# 2020_IST_Respirator_v1_1.net
KiCad netlist of a schematic drawn in EAGLE
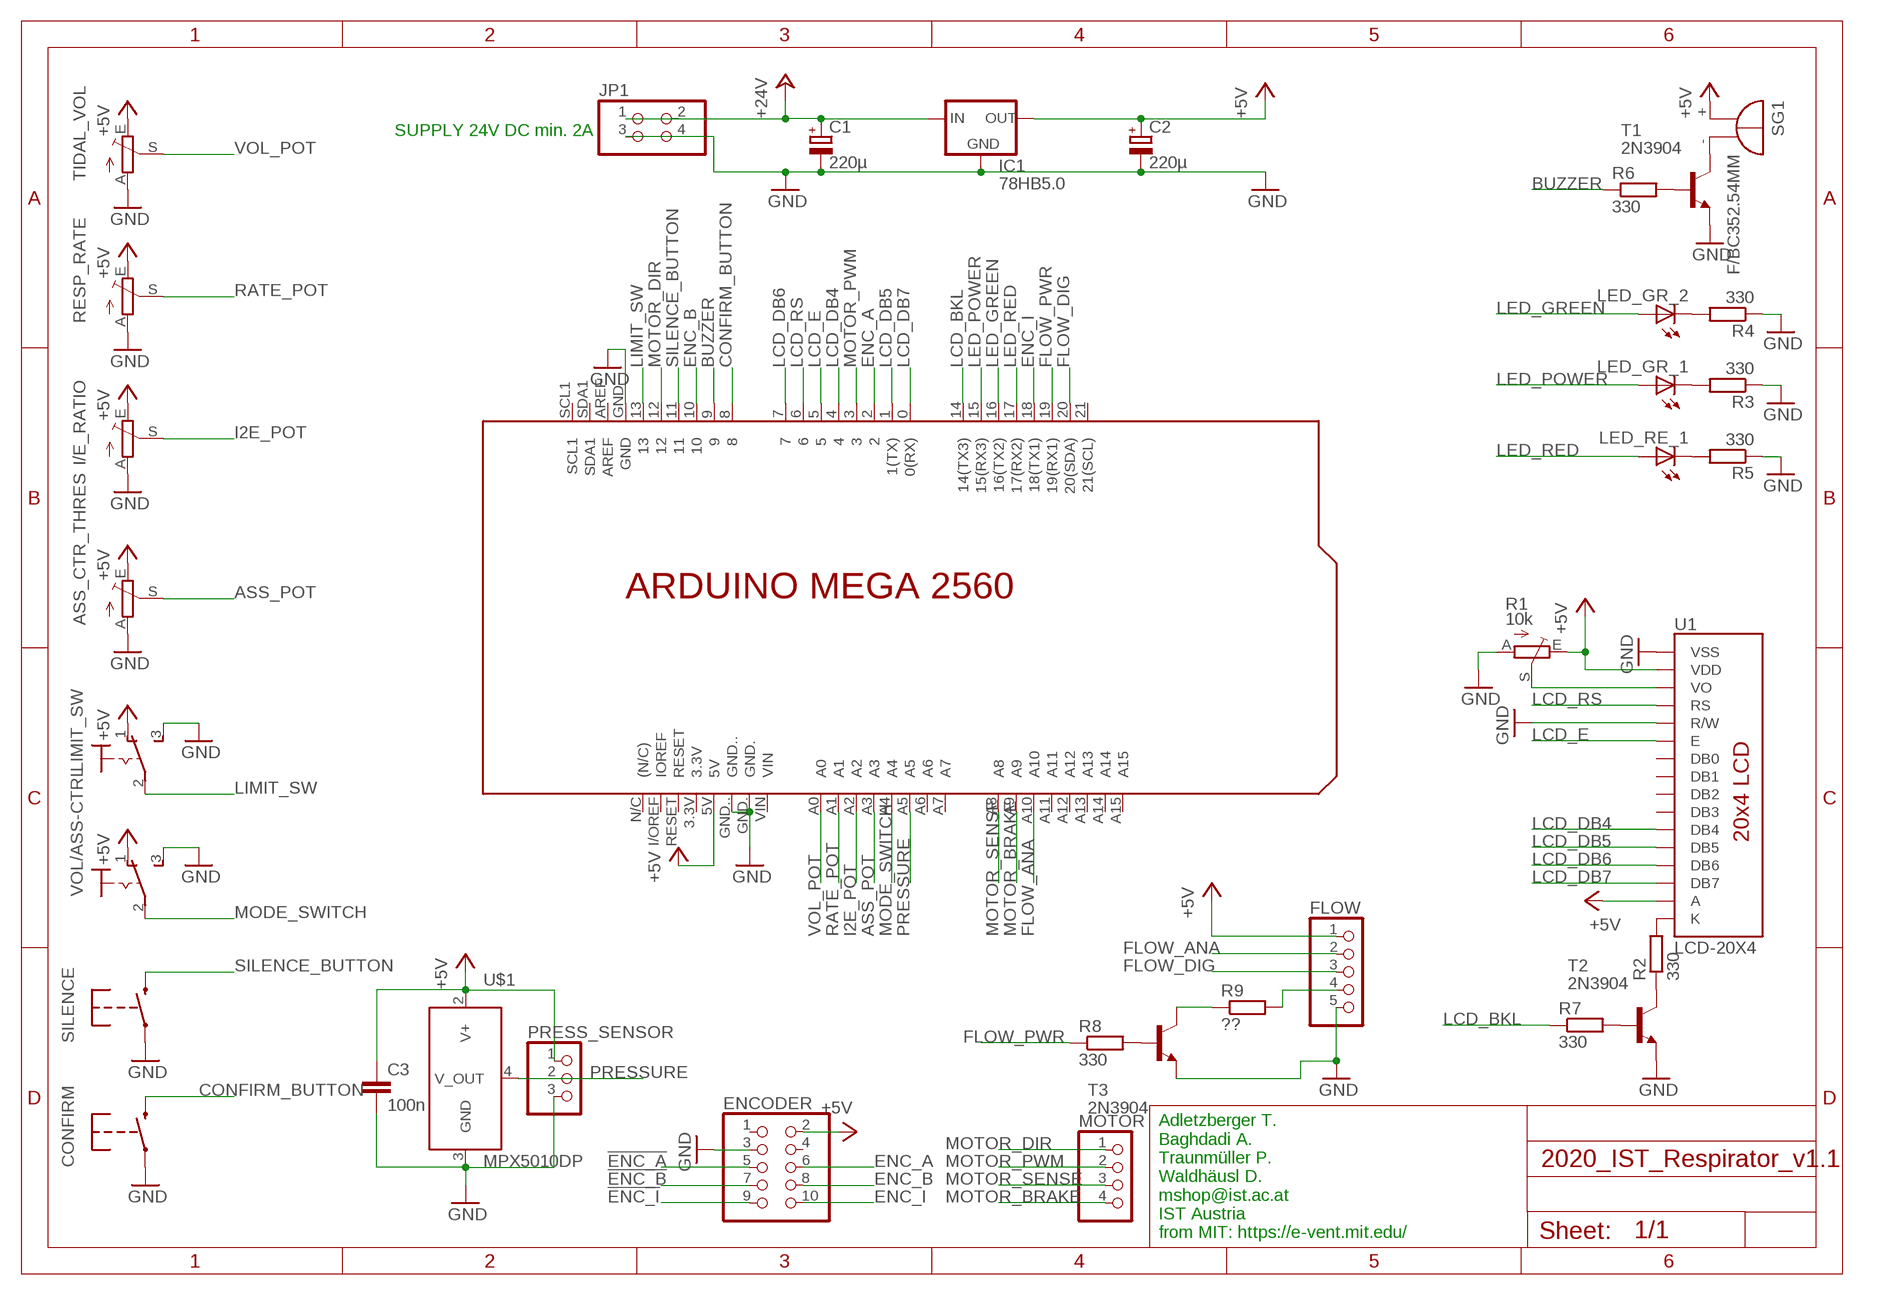
[diagram p0: schematic, sheet 1]

(export (version "E")
  (design (tool "Eeschema 10.0.6"))
  (components
    (comp (ref "ASS_CTR_THRES")
      (value "TRIM_EU-S64W")
      (footprint "eagle-import:S64W")
      (libsource (lib "eagle-import") (part "TRIM_EU-S64W"))
    )
    (comp (ref "C1")
      (value "220µ")
      (footprint "eagle-import:E5-10,5")
      (libsource (lib "eagle-import") (part "CPOL-EUE5-10.5"))
    )
    (comp (ref "C2")
      (value "220µ")
      (footprint "eagle-import:E5-10,5")
      (libsource (lib "eagle-import") (part "CPOL-EUE5-10.5"))
    )
    (comp (ref "C3")
      (value "100n")
      (footprint "eagle-import:C0805")
      (libsource (lib "eagle-import") (part "C-EUC0805"))
    )
    (comp (ref "CONFIRM")
      (value "SWITCH-MOMENTARY-22.54")
      (footprint "eagle-import:TACTILE-2.54MM")
      (libsource (lib "eagle-import") (part "SWITCH-MOMENTARY-22.54"))
    )
    (comp (ref "ENCODER")
      (value "PINHD-2X5")
      (footprint "eagle-import:2X05")
      (libsource (lib "eagle-import") (part "PINHD-2X5"))
    )
    (comp (ref "FLOW")
      (value "PINHD-1X5")
      (footprint "eagle-import:1X05")
      (libsource (lib "eagle-import") (part "PINHD-1X5"))
    )
    (comp (ref "I/E_RATIO")
      (value "TRIM_EU-S64W")
      (footprint "eagle-import:S64W")
      (libsource (lib "eagle-import") (part "TRIM_EU-S64W"))
    )
    (comp (ref "IC1")
      (value "78HB5.0")
      (footprint "eagle-import:78XXS")
      (libsource (lib "eagle-import") (part "78XXS"))
    )
    (comp (ref "JP1")
      (value "PINHD-2X2")
      (footprint "eagle-import:2X02")
      (libsource (lib "eagle-import") (part "PINHD-2X2"))
    )
    (comp (ref "LED_GR_1")
      (value "LED5MM")
      (footprint "eagle-import:LED5MM")
      (libsource (lib "eagle-import") (part "LED5MM"))
    )
    (comp (ref "LED_GR_2")
      (value "LED5MM")
      (footprint "eagle-import:LED5MM")
      (libsource (lib "eagle-import") (part "LED5MM"))
    )
    (comp (ref "LED_RE_1")
      (value "LED5MM")
      (footprint "eagle-import:LED5MM")
      (libsource (lib "eagle-import") (part "LED5MM"))
    )
    (comp (ref "LIMIT_SW")
      (value "320-9162.54MM")
      (footprint "eagle-import:320-916_2.54MM")
      (libsource (lib "eagle-import") (part "320-9162.54MM"))
    )
    (comp (ref "MOTOR")
      (value "PINHD-1X4")
      (footprint "eagle-import:1X04")
      (libsource (lib "eagle-import") (part "PINHD-1X4"))
    )
    (comp (ref "PCB1")
      (value "ARDUINO_MEGA2560_NOTALLPINS")
      (footprint "eagle-import:ARDUINO_MEGA2560_NOTALLPINS")
      (libsource (lib "eagle-import") (part "ARDUINO_MEGA2560_NOTALLPINS"))
    )
    (comp (ref "PRESS_SENSOR")
      (value "PINHD-1X3")
      (footprint "eagle-import:1X03")
      (libsource (lib "eagle-import") (part "PINHD-1X3"))
    )
    (comp (ref "R1")
      (value "10k")
      (footprint "eagle-import:S64W")
      (libsource (lib "eagle-import") (part "TRIM_EU-S64W"))
    )
    (comp (ref "R2")
      (value "330")
      (footprint "eagle-import:0207_10")
      (libsource (lib "eagle-import") (part "R-EU_0207/10"))
    )
    (comp (ref "R3")
      (value "330")
      (footprint "eagle-import:0207_10")
      (libsource (lib "eagle-import") (part "R-EU_0207/10"))
    )
    (comp (ref "R4")
      (value "330")
      (footprint "eagle-import:0207_10")
      (libsource (lib "eagle-import") (part "R-EU_0207/10"))
    )
    (comp (ref "R5")
      (value "330")
      (footprint "eagle-import:0207_10")
      (libsource (lib "eagle-import") (part "R-EU_0207/10"))
    )
    (comp (ref "R6")
      (value "330")
      (footprint "eagle-import:0207_10")
      (libsource (lib "eagle-import") (part "R-EU_0207/10"))
    )
    (comp (ref "R7")
      (value "330")
      (footprint "eagle-import:0207_10")
      (libsource (lib "eagle-import") (part "R-EU_0207/10"))
    )
    (comp (ref "R8")
      (value "330")
      (footprint "eagle-import:0207_10")
      (libsource (lib "eagle-import") (part "R-EU_0207/10"))
    )
    (comp (ref "R9")
      (value "??")
      (footprint "eagle-import:0207_10")
      (libsource (lib "eagle-import") (part "R-EU_0207/10"))
    )
    (comp (ref "RESP_RATE")
      (value "TRIM_EU-S64W")
      (footprint "eagle-import:S64W")
      (libsource (lib "eagle-import") (part "TRIM_EU-S64W"))
    )
    (comp (ref "SG1")
      (value "F/BC352.54MM")
      (footprint "eagle-import:F_BC35_2.54MM")
      (libsource (lib "eagle-import") (part "F/BC352.54MM"))
    )
    (comp (ref "SILENCE")
      (value "SWITCH-MOMENTARY-22.54")
      (footprint "eagle-import:TACTILE-2.54MM")
      (libsource (lib "eagle-import") (part "SWITCH-MOMENTARY-22.54"))
    )
    (comp (ref "T1")
      (value "2N3904")
      (footprint "eagle-import:TO92")
      (libsource (lib "eagle-import") (part "2N3904"))
    )
    (comp (ref "T2")
      (value "2N3904")
      (footprint "eagle-import:TO92")
      (libsource (lib "eagle-import") (part "2N3904"))
    )
    (comp (ref "T3")
      (value "2N3904")
      (footprint "eagle-import:TO92")
      (libsource (lib "eagle-import") (part "2N3904"))
    )
    (comp (ref "TIDAL_VOL")
      (value "TRIM_EU-S64W")
      (footprint "eagle-import:S64W")
      (libsource (lib "eagle-import") (part "TRIM_EU-S64W"))
    )
    (comp (ref "U$1")
      (value "MPX5010DP")
      (footprint "eagle-import:MPX5010DP_SOP482")
      (libsource (lib "eagle-import") (part "MPX5010DP"))
    )
    (comp (ref "U1")
      (value "LCD-20X4")
      (footprint "eagle-import:LCD-20X4")
      (libsource (lib "eagle-import") (part "LCD-20X4"))
    )
    (comp (ref "VOL/ASS-CTRL")
      (value "320-9162.54MM")
      (footprint "eagle-import:320-916_2.54MM")
      (libsource (lib "eagle-import") (part "320-9162.54MM"))
    )
  )
  (nets
    (net (code "1") (name "+5V") (class "Default")
      (node (ref "ASS_CTR_THRES") (pin "E") (pinfunction "E_E") (pintype "passive"))
      (node (ref "C2") (pin "+") (pinfunction "+_+") (pintype "passive"))
      (node (ref "C3") (pin "1") (pinfunction "1_1") (pintype "passive"))
      (node (ref "ENCODER") (pin "2") (pinfunction "2_2") (pintype "passive"))
      (node (ref "FLOW") (pin "1") (pinfunction "1_1") (pintype "passive"))
      (node (ref "I/E_RATIO") (pin "E") (pinfunction "E_E") (pintype "passive"))
      (node (ref "IC1") (pin "OUT") (pinfunction "OUT_OUT") (pintype "passive"))
      (node (ref "LIMIT_SW") (pin "1") (pinfunction "O_1") (pintype "passive"))
      (node (ref "PCB1") (pin "5V") (pinfunction "5V_5V") (pintype "bidirectional"))
      (node (ref "PRESS_SENSOR") (pin "1") (pinfunction "1_1") (pintype "passive"))
      (node (ref "R1") (pin "E") (pinfunction "E_E") (pintype "passive"))
      (node (ref "RESP_RATE") (pin "E") (pinfunction "E_E") (pintype "passive"))
      (node (ref "SG1") (pin "+") (pinfunction "+_+") (pintype "passive"))
      (node (ref "TIDAL_VOL") (pin "E") (pinfunction "E_E") (pintype "passive"))
      (node (ref "U$1") (pin "2") (pinfunction "V+_2") (pintype "power_in"))
      (node (ref "U1") (pin "15") (pinfunction "A_15") (pintype "power_in"))
      (node (ref "U1") (pin "2") (pinfunction "VDD_2") (pintype "power_in"))
      (node (ref "VOL/ASS-CTRL") (pin "1") (pinfunction "O_1") (pintype "passive"))
    )
    (net (code "2") (name "+24V") (class "Default")
      (node (ref "C1") (pin "+") (pinfunction "+_+") (pintype "passive"))
      (node (ref "IC1") (pin "IN") (pinfunction "IN_IN") (pintype "input"))
      (node (ref "JP1") (pin "1") (pinfunction "1_1") (pintype "passive"))
      (node (ref "JP1") (pin "2") (pinfunction "2_2") (pintype "passive"))
    )
    (net (code "3") (name "/ASS_POT") (class "Default")
      (node (ref "ASS_CTR_THRES") (pin "S") (pinfunction "S_S") (pintype "passive"))
      (node (ref "PCB1") (pin "A3") (pinfunction "A3_A3") (pintype "bidirectional"))
    )
    (net (code "4") (name "/BUZZER") (class "Default")
      (node (ref "PCB1") (pin "9") (pinfunction "9_9") (pintype "bidirectional"))
      (node (ref "R6") (pin "1") (pinfunction "1_1") (pintype "passive"))
    )
    (net (code "5") (name "/CONFIRM_BUTTON") (class "Default")
      (node (ref "CONFIRM") (pin "3") (pinfunction "2_3") (pintype "passive"))
      (node (ref "PCB1") (pin "8") (pinfunction "8_8") (pintype "bidirectional"))
    )
    (net (code "6") (name "/ENC_A") (class "Default")
      (node (ref "ENCODER") (pin "6") (pinfunction "6_6") (pintype "passive"))
      (node (ref "PCB1") (pin "2") (pinfunction "2_2") (pintype "bidirectional"))
    )
    (net (code "7") (name "/ENC_B") (class "Default")
      (node (ref "ENCODER") (pin "8") (pinfunction "8_8") (pintype "passive"))
      (node (ref "PCB1") (pin "10") (pinfunction "10_10") (pintype "bidirectional"))
    )
    (net (code "8") (name "/ENC_I") (class "Default")
      (node (ref "ENCODER") (pin "10") (pinfunction "10_10") (pintype "passive"))
      (node (ref "PCB1") (pin "18") (pinfunction "18(TX1)_18") (pintype "bidirectional"))
    )
    (net (code "9") (name "/FLOW_ANA") (class "Default")
      (node (ref "FLOW") (pin "2") (pinfunction "2_2") (pintype "passive"))
      (node (ref "PCB1") (pin "A10") (pinfunction "A10_A10") (pintype "bidirectional"))
    )
    (net (code "10") (name "/FLOW_DIG") (class "Default")
      (node (ref "FLOW") (pin "3") (pinfunction "3_3") (pintype "passive"))
      (node (ref "PCB1") (pin "20") (pinfunction "20(SDA)_20") (pintype "bidirectional"))
    )
    (net (code "11") (name "/FLOW_PWR") (class "Default")
      (node (ref "PCB1") (pin "19") (pinfunction "19(RX1)_19") (pintype "bidirectional"))
      (node (ref "R8") (pin "1") (pinfunction "1_1") (pintype "passive"))
    )
    (net (code "12") (name "/I2E_POT") (class "Default")
      (node (ref "I/E_RATIO") (pin "S") (pinfunction "S_S") (pintype "passive"))
      (node (ref "PCB1") (pin "A2") (pinfunction "A2_A2") (pintype "bidirectional"))
    )
    (net (code "13") (name "/LCD_BKL") (class "Default")
      (node (ref "PCB1") (pin "14") (pinfunction "14(TX3)_14") (pintype "bidirectional"))
      (node (ref "R7") (pin "1") (pinfunction "1_1") (pintype "passive"))
    )
    (net (code "14") (name "/LCD_DB4") (class "Default")
      (node (ref "PCB1") (pin "4") (pinfunction "4_4") (pintype "bidirectional"))
      (node (ref "U1") (pin "11") (pinfunction "DB4_11") (pintype "bidirectional"))
    )
    (net (code "15") (name "/LCD_DB5") (class "Default")
      (node (ref "PCB1") (pin "1") (pinfunction "1(TX)_1") (pintype "bidirectional"))
      (node (ref "U1") (pin "12") (pinfunction "DB5_12") (pintype "bidirectional"))
    )
    (net (code "16") (name "/LCD_DB6") (class "Default")
      (node (ref "PCB1") (pin "7") (pinfunction "7_7") (pintype "bidirectional"))
      (node (ref "U1") (pin "13") (pinfunction "DB6_13") (pintype "bidirectional"))
    )
    (net (code "17") (name "/LCD_DB7") (class "Default")
      (node (ref "PCB1") (pin "0") (pinfunction "0(RX)_0") (pintype "bidirectional"))
      (node (ref "U1") (pin "14") (pinfunction "DB7_14") (pintype "bidirectional"))
    )
    (net (code "18") (name "/LCD_E") (class "Default")
      (node (ref "PCB1") (pin "5") (pinfunction "5_5") (pintype "bidirectional"))
      (node (ref "U1") (pin "6") (pinfunction "E_6") (pintype "input"))
    )
    (net (code "19") (name "/LCD_RS") (class "Default")
      (node (ref "PCB1") (pin "6") (pinfunction "6_6") (pintype "bidirectional"))
      (node (ref "U1") (pin "4") (pinfunction "RS_4") (pintype "input"))
    )
    (net (code "20") (name "/LED_GREEN") (class "Default")
      (node (ref "LED_GR_2") (pin "A") (pinfunction "A_A") (pintype "passive"))
      (node (ref "PCB1") (pin "16") (pinfunction "16(TX2)_16") (pintype "bidirectional"))
    )
    (net (code "21") (name "/LED_POWER") (class "Default")
      (node (ref "LED_GR_1") (pin "A") (pinfunction "A_A") (pintype "passive"))
      (node (ref "PCB1") (pin "15") (pinfunction "15(RX3)_15") (pintype "bidirectional"))
    )
    (net (code "22") (name "/LED_RED") (class "Default")
      (node (ref "LED_RE_1") (pin "A") (pinfunction "A_A") (pintype "passive"))
      (node (ref "PCB1") (pin "17") (pinfunction "17(RX2)_17") (pintype "bidirectional"))
    )
    (net (code "23") (name "/LIMIT_SW") (class "Default")
      (node (ref "LIMIT_SW") (pin "2") (pinfunction "P_2") (pintype "passive"))
      (node (ref "PCB1") (pin "13") (pinfunction "13_13") (pintype "bidirectional"))
    )
    (net (code "24") (name "/MODE_SWITCH") (class "Default")
      (node (ref "PCB1") (pin "A4") (pinfunction "A4_A4") (pintype "bidirectional"))
      (node (ref "VOL/ASS-CTRL") (pin "2") (pinfunction "P_2") (pintype "passive"))
    )
    (net (code "25") (name "/MOTOR_BRAKE") (class "Default")
      (node (ref "MOTOR") (pin "4") (pinfunction "4_4") (pintype "passive"))
      (node (ref "PCB1") (pin "A9") (pinfunction "A9_A9") (pintype "bidirectional"))
    )
    (net (code "26") (name "/MOTOR_DIR") (class "Default")
      (node (ref "MOTOR") (pin "1") (pinfunction "1_1") (pintype "passive"))
      (node (ref "PCB1") (pin "12") (pinfunction "12_12") (pintype "bidirectional"))
    )
    (net (code "27") (name "/MOTOR_PWM") (class "Default")
      (node (ref "MOTOR") (pin "2") (pinfunction "2_2") (pintype "passive"))
      (node (ref "PCB1") (pin "3") (pinfunction "3_3") (pintype "bidirectional"))
    )
    (net (code "28") (name "/MOTOR_SENSE") (class "Default")
      (node (ref "MOTOR") (pin "3") (pinfunction "3_3") (pintype "passive"))
      (node (ref "PCB1") (pin "A8") (pinfunction "A8_A8") (pintype "bidirectional"))
    )
    (net (code "29") (name "/PRESSURE") (class "Default")
      (node (ref "PCB1") (pin "A5") (pinfunction "A5_A5") (pintype "bidirectional"))
      (node (ref "PRESS_SENSOR") (pin "2") (pinfunction "2_2") (pintype "passive"))
      (node (ref "U$1") (pin "4") (pinfunction "V_OUT_4") (pintype "power_in"))
    )
    (net (code "30") (name "/RATE_POT") (class "Default")
      (node (ref "PCB1") (pin "A1") (pinfunction "A1_A1") (pintype "bidirectional"))
      (node (ref "RESP_RATE") (pin "S") (pinfunction "S_S") (pintype "passive"))
    )
    (net (code "31") (name "/SILENCE_BUTTON") (class "Default")
      (node (ref "PCB1") (pin "11") (pinfunction "11_11") (pintype "bidirectional"))
      (node (ref "SILENCE") (pin "3") (pinfunction "2_3") (pintype "passive"))
    )
    (net (code "32") (name "/VOL_POT") (class "Default")
      (node (ref "PCB1") (pin "A0") (pinfunction "A0_A0") (pintype "bidirectional"))
      (node (ref "TIDAL_VOL") (pin "S") (pinfunction "S_S") (pintype "passive"))
    )
    (net (code "33") (name "/~{ENC_A}") (class "Default")
      (node (ref "ENCODER") (pin "5") (pinfunction "5_5") (pintype "passive"))
    )
    (net (code "34") (name "/~{ENC_B}") (class "Default")
      (node (ref "ENCODER") (pin "7") (pinfunction "7_7") (pintype "passive"))
    )
    (net (code "35") (name "/~{ENC_I}") (class "Default")
      (node (ref "ENCODER") (pin "9") (pinfunction "9_9") (pintype "passive"))
    )
    (net (code "36") (name "GND") (class "Default")
      (node (ref "ASS_CTR_THRES") (pin "A") (pinfunction "A_A") (pintype "passive"))
      (node (ref "C1") (pin "-") (pinfunction "-_-") (pintype "passive"))
      (node (ref "C2") (pin "-") (pinfunction "-_-") (pintype "passive"))
      (node (ref "C3") (pin "2") (pinfunction "2_2") (pintype "passive"))
      (node (ref "CONFIRM") (pin "1") (pinfunction "1_1") (pintype "passive"))
      (node (ref "ENCODER") (pin "3") (pinfunction "3_3") (pintype "passive"))
      (node (ref "FLOW") (pin "5") (pinfunction "5_5") (pintype "passive"))
      (node (ref "I/E_RATIO") (pin "A") (pinfunction "A_A") (pintype "passive"))
      (node (ref "IC1") (pin "GND") (pinfunction "GND_GND") (pintype "input"))
      (node (ref "JP1") (pin "3") (pinfunction "3_3") (pintype "passive"))
      (node (ref "JP1") (pin "4") (pinfunction "4_4") (pintype "passive"))
      (node (ref "LIMIT_SW") (pin "3") (pinfunction "S_3") (pintype "passive"))
      (node (ref "PCB1") (pin "GND") (pinfunction "GND_GND") (pintype "bidirectional"))
      (node (ref "PCB1") (pin "GND.") (pinfunction "GND._GND.") (pintype "bidirectional"))
      (node (ref "PCB1") (pin "GND..") (pinfunction "GND.._GND..") (pintype "bidirectional"))
      (node (ref "PRESS_SENSOR") (pin "3") (pinfunction "3_3") (pintype "passive"))
      (node (ref "R1") (pin "A") (pinfunction "A_A") (pintype "passive"))
      (node (ref "R3") (pin "1") (pinfunction "1_1") (pintype "passive"))
      (node (ref "R4") (pin "1") (pinfunction "1_1") (pintype "passive"))
      (node (ref "R5") (pin "1") (pinfunction "1_1") (pintype "passive"))
      (node (ref "RESP_RATE") (pin "A") (pinfunction "A_A") (pintype "passive"))
      (node (ref "SILENCE") (pin "1") (pinfunction "1_1") (pintype "passive"))
      (node (ref "T1") (pin "3") (pinfunction "E_3") (pintype "passive"))
      (node (ref "T2") (pin "3") (pinfunction "E_3") (pintype "passive"))
      (node (ref "T3") (pin "3") (pinfunction "E_3") (pintype "passive"))
      (node (ref "TIDAL_VOL") (pin "A") (pinfunction "A_A") (pintype "passive"))
      (node (ref "U$1") (pin "3") (pinfunction "GND_3") (pintype "bidirectional"))
      (node (ref "U1") (pin "1") (pinfunction "VSS_1") (pintype "power_in"))
      (node (ref "U1") (pin "5") (pinfunction "R/W_5") (pintype "input"))
      (node (ref "VOL/ASS-CTRL") (pin "3") (pinfunction "S_3") (pintype "passive"))
    )
    (net (code "37") (name "Net-(FLOW-Pad4)") (class "Default")
      (node (ref "FLOW") (pin "4") (pinfunction "4_4") (pintype "passive"))
      (node (ref "R9") (pin "2") (pinfunction "2_2") (pintype "passive"))
    )
    (net (code "38") (name "Net-(LED_GR_1-C)") (class "Default")
      (node (ref "LED_GR_1") (pin "K") (pinfunction "C_K") (pintype "passive"))
      (node (ref "R3") (pin "2") (pinfunction "2_2") (pintype "passive"))
    )
    (net (code "39") (name "Net-(LED_GR_2-C)") (class "Default")
      (node (ref "LED_GR_2") (pin "K") (pinfunction "C_K") (pintype "passive"))
      (node (ref "R4") (pin "2") (pinfunction "2_2") (pintype "passive"))
    )
    (net (code "40") (name "Net-(LED_RE_1-C)") (class "Default")
      (node (ref "LED_RE_1") (pin "K") (pinfunction "C_K") (pintype "passive"))
      (node (ref "R5") (pin "2") (pinfunction "2_2") (pintype "passive"))
    )
    (net (code "41") (name "Net-(T1-B)") (class "Default")
      (node (ref "R6") (pin "2") (pinfunction "2_2") (pintype "passive"))
      (node (ref "T1") (pin "2") (pinfunction "B_2") (pintype "passive"))
    )
    (net (code "42") (name "Net-(T1-C)") (class "Default")
      (node (ref "SG1") (pin "-") (pinfunction "-_-") (pintype "passive"))
      (node (ref "T1") (pin "1") (pinfunction "C_1") (pintype "passive"))
    )
    (net (code "43") (name "Net-(T2-B)") (class "Default")
      (node (ref "R7") (pin "2") (pinfunction "2_2") (pintype "passive"))
      (node (ref "T2") (pin "2") (pinfunction "B_2") (pintype "passive"))
    )
    (net (code "44") (name "Net-(T2-C)") (class "Default")
      (node (ref "R2") (pin "1") (pinfunction "1_1") (pintype "passive"))
      (node (ref "T2") (pin "1") (pinfunction "C_1") (pintype "passive"))
    )
    (net (code "45") (name "Net-(T3-B)") (class "Default")
      (node (ref "R8") (pin "2") (pinfunction "2_2") (pintype "passive"))
      (node (ref "T3") (pin "2") (pinfunction "B_2") (pintype "passive"))
    )
    (net (code "46") (name "Net-(T3-C)") (class "Default")
      (node (ref "R9") (pin "1") (pinfunction "1_1") (pintype "passive"))
      (node (ref "T3") (pin "1") (pinfunction "C_1") (pintype "passive"))
    )
    (net (code "47") (name "Net-(U1-K)") (class "Default")
      (node (ref "R2") (pin "2") (pinfunction "2_2") (pintype "passive"))
      (node (ref "U1") (pin "16") (pinfunction "K_16") (pintype "power_in"))
    )
    (net (code "48") (name "Net-(U1-VO)") (class "Default")
      (node (ref "R1") (pin "S") (pinfunction "S_S") (pintype "passive"))
      (node (ref "U1") (pin "3") (pinfunction "VO_3") (pintype "bidirectional"))
    )
    (net (code "49") (name "unconnected-(ENCODER-Pad1)") (class "Default")
      (node (ref "ENCODER") (pin "1") (pinfunction "1_1") (pintype "passive"))
    )
    (net (code "50") (name "unconnected-(ENCODER-Pad4)") (class "Default")
      (node (ref "ENCODER") (pin "4") (pinfunction "4_4") (pintype "passive"))
    )
    (net (code "51") (name "unconnected-(PCB1-(N{slash}C)-PadN{slash}C)") (class "Default")
      (node (ref "PCB1") (pin "N/C") (pinfunction "(N/C)_N/C") (pintype "bidirectional"))
    )
    (net (code "52") (name "unconnected-(PCB1-21(SCL)-Pad21)") (class "Default")
      (node (ref "PCB1") (pin "21") (pinfunction "21(SCL)_21") (pintype "bidirectional"))
    )
    (net (code "53") (name "unconnected-(PCB1-IOREF-PadI{slash}OREF)") (class "Default")
      (node (ref "PCB1") (pin "I/OREF") (pinfunction "IOREF_I/OREF") (pintype "bidirectional"))
    )
    (net (code "54") (name "unconnected-(PCB1-Pad3.3V)") (class "Default")
      (node (ref "PCB1") (pin "3.3V") (pinfunction "3.3V_3.3V") (pintype "bidirectional"))
    )
    (net (code "55") (name "unconnected-(PCB1-PadA6)") (class "Default")
      (node (ref "PCB1") (pin "A6") (pinfunction "A6_A6") (pintype "bidirectional"))
    )
    (net (code "56") (name "unconnected-(PCB1-PadA7)") (class "Default")
      (node (ref "PCB1") (pin "A7") (pinfunction "A7_A7") (pintype "bidirectional"))
    )
    (net (code "57") (name "unconnected-(PCB1-PadA11)") (class "Default")
      (node (ref "PCB1") (pin "A11") (pinfunction "A11_A11") (pintype "bidirectional"))
    )
    (net (code "58") (name "unconnected-(PCB1-PadA12)") (class "Default")
      (node (ref "PCB1") (pin "A12") (pinfunction "A12_A12") (pintype "bidirectional"))
    )
    (net (code "59") (name "unconnected-(PCB1-PadA13)") (class "Default")
      (node (ref "PCB1") (pin "A13") (pinfunction "A13_A13") (pintype "bidirectional"))
    )
    (net (code "60") (name "unconnected-(PCB1-PadA14)") (class "Default")
      (node (ref "PCB1") (pin "A14") (pinfunction "A14_A14") (pintype "bidirectional"))
    )
    (net (code "61") (name "unconnected-(PCB1-PadA15)") (class "Default")
      (node (ref "PCB1") (pin "A15") (pinfunction "A15_A15") (pintype "bidirectional"))
    )
    (net (code "62") (name "unconnected-(PCB1-PadAREF)") (class "Default")
      (node (ref "PCB1") (pin "AREF") (pinfunction "AREF_AREF") (pintype "bidirectional"))
    )
    (net (code "63") (name "unconnected-(PCB1-PadRESET)") (class "Default")
      (node (ref "PCB1") (pin "RESET") (pinfunction "RESET_RESET") (pintype "bidirectional"))
    )
    (net (code "64") (name "unconnected-(PCB1-PadSCL1)") (class "Default")
      (node (ref "PCB1") (pin "SCL1") (pinfunction "SCL1_SCL1") (pintype "bidirectional"))
    )
    (net (code "65") (name "unconnected-(PCB1-PadSDA1)") (class "Default")
      (node (ref "PCB1") (pin "SDA1") (pinfunction "SDA1_SDA1") (pintype "bidirectional"))
    )
    (net (code "66") (name "unconnected-(PCB1-PadVIN)") (class "Default")
      (node (ref "PCB1") (pin "VIN") (pinfunction "VIN_VIN") (pintype "bidirectional"))
    )
    (net (code "67") (name "unconnected-(U1-DB0-Pad7)") (class "Default")
      (node (ref "U1") (pin "7") (pinfunction "DB0_7") (pintype "bidirectional"))
    )
    (net (code "68") (name "unconnected-(U1-DB1-Pad8)") (class "Default")
      (node (ref "U1") (pin "8") (pinfunction "DB1_8") (pintype "bidirectional"))
    )
    (net (code "69") (name "unconnected-(U1-DB2-Pad9)") (class "Default")
      (node (ref "U1") (pin "9") (pinfunction "DB2_9") (pintype "bidirectional"))
    )
    (net (code "70") (name "unconnected-(U1-DB3-Pad10)") (class "Default")
      (node (ref "U1") (pin "10") (pinfunction "DB3_10") (pintype "bidirectional"))
    )
  )
)
